# TAUV-Disconnect.net
KiCad netlist of a schematic drawn in Altium Designer
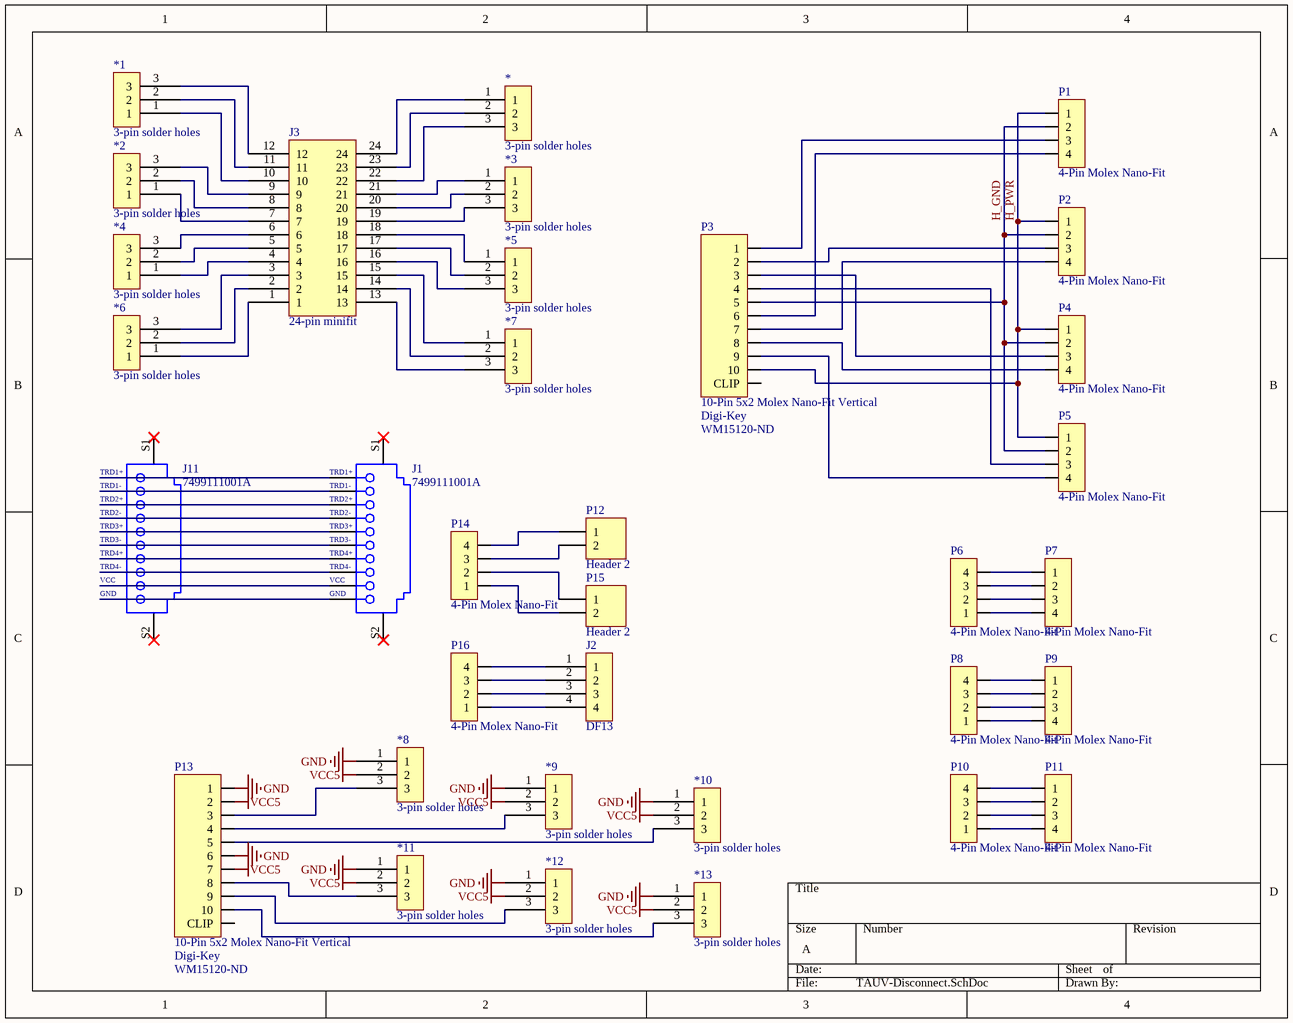
[diagram p0: TAUV-Disconnect.SchDoc]

(export (version "E")
  (design (tool "Eeschema 10.0.6"))
  (components
    (comp (ref "*")
      (value "3-pin solder holes")
      (footprint "3-PIN SOLDER HOLES")
      (libsource (lib "Tauv-Lib") (part "3-pin solder holes"))
    )
    (comp (ref "*1")
      (value "3-pin solder holes")
      (footprint "3-PIN SOLDER HOLES")
      (libsource (lib "") (part "3-pin solder holes_1"))
    )
    (comp (ref "*2")
      (value "3-pin solder holes")
      (footprint "3-PIN SOLDER HOLES")
      (libsource (lib "") (part "3-pin solder holes_1"))
    )
    (comp (ref "*3")
      (value "3-pin solder holes")
      (footprint "3-PIN SOLDER HOLES")
      (libsource (lib "Tauv-Lib") (part "3-pin solder holes"))
    )
    (comp (ref "*4")
      (value "3-pin solder holes")
      (footprint "3-PIN SOLDER HOLES")
      (libsource (lib "") (part "3-pin solder holes_1"))
    )
    (comp (ref "*5")
      (value "3-pin solder holes")
      (footprint "3-PIN SOLDER HOLES")
      (libsource (lib "Tauv-Lib") (part "3-pin solder holes"))
    )
    (comp (ref "*6")
      (value "3-pin solder holes")
      (footprint "3-PIN SOLDER HOLES")
      (libsource (lib "") (part "3-pin solder holes_1"))
    )
    (comp (ref "*7")
      (value "3-pin solder holes")
      (footprint "3-PIN SOLDER HOLES")
      (libsource (lib "Tauv-Lib") (part "3-pin solder holes"))
    )
    (comp (ref "*8")
      (value "3-pin solder holes")
      (footprint "3-PIN SOLDER HOLES - small")
      (libsource (lib "Tauv-Lib") (part "3-pin solder holes"))
    )
    (comp (ref "*9")
      (value "3-pin solder holes")
      (footprint "3-PIN SOLDER HOLES - small")
      (libsource (lib "Tauv-Lib") (part "3-pin solder holes"))
    )
    (comp (ref "*10")
      (value "3-pin solder holes")
      (footprint "3-PIN SOLDER HOLES - small")
      (libsource (lib "Tauv-Lib") (part "3-pin solder holes"))
    )
    (comp (ref "*11")
      (value "3-pin solder holes")
      (footprint "3-PIN SOLDER HOLES - small")
      (libsource (lib "Tauv-Lib") (part "3-pin solder holes"))
    )
    (comp (ref "*12")
      (value "3-pin solder holes")
      (footprint "3-PIN SOLDER HOLES - small")
      (libsource (lib "Tauv-Lib") (part "3-pin solder holes"))
    )
    (comp (ref "*13")
      (value "3-pin solder holes")
      (footprint "3-PIN SOLDER HOLES - small")
      (libsource (lib "Tauv-Lib") (part "3-pin solder holes"))
    )
    (comp (ref "J1")
      (value "7499111001A")
      (footprint "WE-7499111001A_V")
      (description "RJ45 LAN Transformer, Modular JACK, 0 to 70 degC, 10-Pin THD, RoHS, Tube")
      (libsource (lib "Altium Content Vault") (part "RJ45-10-2SHLD_A"))
    )
    (comp (ref "J2")
      (value "DF13")
      (footprint "4-pin DF13 vertical smd")
      (description "H126000CT-ND")
      (libsource (lib "Tauv-Lib") (part "4-pin DF13 vertical smd"))
    )
    (comp (ref "J3")
      (value "24-pin minifit")
      (footprint "24-PIN MINIFIT VERT")
      (description "RA: WM21362-ND\r\nVERT: WM3811-ND")
      (libsource (lib "Tauv-Lib") (part "24-pin minifit RA"))
    )
    (comp (ref "J11")
      (value "7499111001A")
      (footprint "WE-7499111001A_V")
      (description "RJ45 LAN Transformer, Modular JACK, 0 to 70 degC, 10-Pin THD, RoHS, Tube")
      (libsource (lib "Altium Content Vault") (part "RJ45-10-2SHLD_A"))
    )
    (comp (ref "P1")
      (value "4-Pin Molex Nano-Fit")
      (footprint "MOLEX NANO-FIT 1X4 - Vertical")
      (description "NanoFit ST Hdr TH SR 4Ckt")
      (fields (field (name "MANUFACTURER") "Molex") (field (name "PART NUMBER") "105313-1204"))
      (libsource (lib "") (part "4-Pin Nano-Fit Throughole Vertical_1"))
    )
    (comp (ref "P2")
      (value "4-Pin Molex Nano-Fit")
      (footprint "MOLEX NANO-FIT 1X4 - Vertical")
      (description "NanoFit ST Hdr TH SR 4Ckt")
      (fields (field (name "MANUFACTURER") "Molex") (field (name "PART NUMBER") "105313-1204"))
      (libsource (lib "") (part "4-Pin Nano-Fit Throughole Vertical_1"))
    )
    (comp (ref "P3")
      (value "10-Pin 5x2 Molex Nano-Fit Vertical")
      (footprint "MOLEX NANO-FIT 2x5 - Vertical")
      (description "NanoFit VT Hdr TH DR 10Ckt")
      (fields
        (field (name "PART NUMBER") "105314-1216")
        (field (name "MANUFACTURER") "Molex")
        (field (name "SUPPLIER 1") "Digi-Key")
        (field (name "SUPPLIER PART NUMBER 1") "WM15120-ND")
      )
      (libsource (lib "CMR_Connectors") (part "10-Pin 2-Row Nano-Fit_Vertical"))
    )
    (comp (ref "P4")
      (value "4-Pin Molex Nano-Fit")
      (footprint "MOLEX NANO-FIT 1X4 - Vertical")
      (description "NanoFit ST Hdr TH SR 4Ckt")
      (fields (field (name "MANUFACTURER") "Molex") (field (name "PART NUMBER") "105313-1204"))
      (libsource (lib "") (part "4-Pin Nano-Fit Throughole Vertical_1"))
    )
    (comp (ref "P5")
      (value "4-Pin Molex Nano-Fit")
      (footprint "MOLEX NANO-FIT 1X4 - Vertical")
      (description "NanoFit ST Hdr TH SR 4Ckt")
      (fields (field (name "MANUFACTURER") "Molex") (field (name "PART NUMBER") "105313-1204"))
      (libsource (lib "") (part "4-Pin Nano-Fit Throughole Vertical_1"))
    )
    (comp (ref "P6")
      (value "4-Pin Molex Nano-Fit")
      (footprint "MOLEX NANO-FIT 1X4 - Vertical")
      (description "NanoFit ST Hdr TH SR 4Ckt")
      (fields (field (name "MANUFACTURER") "Molex") (field (name "PART NUMBER") "105313-1204"))
      (libsource (lib "CMR_Connectors") (part "4-Pin Nano-Fit Throughole Vertical"))
    )
    (comp (ref "P7")
      (value "4-Pin Molex Nano-Fit")
      (footprint "MOLEX NANO-FIT 1X4 - Vertical")
      (description "NanoFit ST Hdr TH SR 4Ckt")
      (fields (field (name "MANUFACTURER") "Molex") (field (name "PART NUMBER") "105313-1204"))
      (libsource (lib "") (part "4-Pin Nano-Fit Throughole Vertical_1"))
    )
    (comp (ref "P8")
      (value "4-Pin Molex Nano-Fit")
      (footprint "MOLEX NANO-FIT 1X4 - Vertical")
      (description "NanoFit ST Hdr TH SR 4Ckt")
      (fields (field (name "MANUFACTURER") "Molex") (field (name "PART NUMBER") "105313-1204"))
      (libsource (lib "CMR_Connectors") (part "4-Pin Nano-Fit Throughole Vertical"))
    )
    (comp (ref "P9")
      (value "4-Pin Molex Nano-Fit")
      (footprint "MOLEX NANO-FIT 1X4 - Vertical")
      (description "NanoFit ST Hdr TH SR 4Ckt")
      (fields (field (name "MANUFACTURER") "Molex") (field (name "PART NUMBER") "105313-1204"))
      (libsource (lib "") (part "4-Pin Nano-Fit Throughole Vertical_1"))
    )
    (comp (ref "P10")
      (value "4-Pin Molex Nano-Fit")
      (footprint "MOLEX NANO-FIT 1X4 - Vertical")
      (description "NanoFit ST Hdr TH SR 4Ckt")
      (fields (field (name "MANUFACTURER") "Molex") (field (name "PART NUMBER") "105313-1204"))
      (libsource (lib "CMR_Connectors") (part "4-Pin Nano-Fit Throughole Vertical"))
    )
    (comp (ref "P11")
      (value "4-Pin Molex Nano-Fit")
      (footprint "MOLEX NANO-FIT 1X4 - Vertical")
      (description "NanoFit ST Hdr TH SR 4Ckt")
      (fields (field (name "MANUFACTURER") "Molex") (field (name "PART NUMBER") "105313-1204"))
      (libsource (lib "") (part "4-Pin Nano-Fit Throughole Vertical_1"))
    )
    (comp (ref "P12")
      (value "Header 2")
      (footprint "HDR1X2")
      (description "Header, 2-Pin")
      (fields (field (name "PUBLISHER") "Altium Limited"))
      (libsource (lib "Miscellaneous Connectors") (part "Header 2"))
    )
    (comp (ref "P13")
      (value "10-Pin 5x2 Molex Nano-Fit Vertical")
      (footprint "MOLEX NANO-FIT 2x5 - Vertical")
      (description "NanoFit VT Hdr TH DR 10Ckt")
      (fields
        (field (name "PART NUMBER") "105314-1216")
        (field (name "MANUFACTURER") "Molex")
        (field (name "SUPPLIER 1") "Digi-Key")
        (field (name "SUPPLIER PART NUMBER 1") "WM15120-ND")
      )
      (libsource (lib "CMR_Connectors") (part "10-Pin 2-Row Nano-Fit_Vertical"))
    )
    (comp (ref "P14")
      (value "4-Pin Molex Nano-Fit")
      (footprint "MOLEX NANO-FIT 1X4 - Vertical")
      (description "NanoFit ST Hdr TH SR 4Ckt")
      (fields (field (name "MANUFACTURER") "Molex") (field (name "PART NUMBER") "105313-1204"))
      (libsource (lib "CMR_Connectors") (part "4-Pin Nano-Fit Throughole Vertical"))
    )
    (comp (ref "P15")
      (value "Header 2")
      (footprint "HDR1X2")
      (description "Header, 2-Pin")
      (fields (field (name "PUBLISHER") "Altium Limited"))
      (libsource (lib "Miscellaneous Connectors") (part "Header 2"))
    )
    (comp (ref "P16")
      (value "4-Pin Molex Nano-Fit")
      (footprint "MOLEX NANO-FIT 1X4 - Vertical")
      (description "NanoFit ST Hdr TH SR 4Ckt")
      (fields (field (name "MANUFACTURER") "Molex") (field (name "PART NUMBER") "105313-1204"))
      (libsource (lib "CMR_Connectors") (part "4-Pin Nano-Fit Throughole Vertical"))
    )
  )
  (nets
    (net (code "1") (name "/H_GND") (class "Default")
      (node (ref "P1") (pin "2") (pinfunction "2_2") (pintype "passive"))
      (node (ref "P2") (pin "2") (pinfunction "2_2") (pintype "passive"))
      (node (ref "P3") (pin "5") (pinfunction "5_5") (pintype "passive"))
      (node (ref "P4") (pin "2") (pinfunction "2_2") (pintype "passive"))
      (node (ref "P5") (pin "2") (pinfunction "2_2") (pintype "passive"))
    )
    (net (code "2") (name "/H_PWR") (class "Default")
      (node (ref "P1") (pin "1") (pinfunction "1_1") (pintype "passive"))
      (node (ref "P2") (pin "1") (pinfunction "1_1") (pintype "passive"))
      (node (ref "P3") (pin "10") (pinfunction "10_10") (pintype "passive"))
      (node (ref "P4") (pin "1") (pinfunction "1_1") (pintype "passive"))
      (node (ref "P5") (pin "1") (pinfunction "1_1") (pintype "passive"))
    )
    (net (code "3") (name "GND") (class "Default")
      (node (ref "*10") (pin "1") (pinfunction "1_1") (pintype "passive"))
      (node (ref "*11") (pin "1") (pinfunction "1_1") (pintype "passive"))
      (node (ref "*12") (pin "1") (pinfunction "1_1") (pintype "passive"))
      (node (ref "*13") (pin "1") (pinfunction "1_1") (pintype "passive"))
      (node (ref "*8") (pin "1") (pinfunction "1_1") (pintype "passive"))
      (node (ref "*9") (pin "1") (pinfunction "1_1") (pintype "passive"))
      (node (ref "P13") (pin "1") (pinfunction "1_1") (pintype "passive"))
      (node (ref "P13") (pin "6") (pinfunction "6_6") (pintype "passive"))
    )
    (net (code "4") (name "Net-(*-Pad1)") (class "Default")
      (node (ref "*") (pin "1") (pinfunction "1_1") (pintype "passive"))
      (node (ref "J3") (pin "24") (pinfunction "24_24") (pintype "passive"))
    )
    (net (code "5") (name "Net-(*-Pad2)") (class "Default")
      (node (ref "*") (pin "2") (pinfunction "2_2") (pintype "passive"))
      (node (ref "J3") (pin "23") (pinfunction "23_23") (pintype "passive"))
    )
    (net (code "6") (name "Net-(*-Pad3)") (class "Default")
      (node (ref "*") (pin "3") (pinfunction "3_3") (pintype "passive"))
      (node (ref "J3") (pin "22") (pinfunction "22_22") (pintype "passive"))
    )
    (net (code "7") (name "Net-(*1-Pad1)") (class "Default")
      (node (ref "*1") (pin "1") (pinfunction "1_1") (pintype "passive"))
      (node (ref "J3") (pin "10") (pinfunction "10_10") (pintype "passive"))
    )
    (net (code "8") (name "Net-(*1-Pad2)") (class "Default")
      (node (ref "*1") (pin "2") (pinfunction "2_2") (pintype "passive"))
      (node (ref "J3") (pin "11") (pinfunction "11_11") (pintype "passive"))
    )
    (net (code "9") (name "Net-(*1-Pad3)") (class "Default")
      (node (ref "*1") (pin "3") (pinfunction "3_3") (pintype "passive"))
      (node (ref "J3") (pin "12") (pinfunction "12_12") (pintype "passive"))
    )
    (net (code "10") (name "Net-(*2-Pad1)") (class "Default")
      (node (ref "*2") (pin "1") (pinfunction "1_1") (pintype "passive"))
      (node (ref "J3") (pin "7") (pinfunction "7_7") (pintype "passive"))
    )
    (net (code "11") (name "Net-(*2-Pad2)") (class "Default")
      (node (ref "*2") (pin "2") (pinfunction "2_2") (pintype "passive"))
      (node (ref "J3") (pin "8") (pinfunction "8_8") (pintype "passive"))
    )
    (net (code "12") (name "Net-(*2-Pad3)") (class "Default")
      (node (ref "*2") (pin "3") (pinfunction "3_3") (pintype "passive"))
      (node (ref "J3") (pin "9") (pinfunction "9_9") (pintype "passive"))
    )
    (net (code "13") (name "Net-(*3-Pad1)") (class "Default")
      (node (ref "*3") (pin "1") (pinfunction "1_1") (pintype "passive"))
      (node (ref "J3") (pin "21") (pinfunction "21_21") (pintype "passive"))
    )
    (net (code "14") (name "Net-(*3-Pad2)") (class "Default")
      (node (ref "*3") (pin "2") (pinfunction "2_2") (pintype "passive"))
      (node (ref "J3") (pin "20") (pinfunction "20_20") (pintype "passive"))
    )
    (net (code "15") (name "Net-(*3-Pad3)") (class "Default")
      (node (ref "*3") (pin "3") (pinfunction "3_3") (pintype "passive"))
      (node (ref "J3") (pin "19") (pinfunction "19_19") (pintype "passive"))
    )
    (net (code "16") (name "Net-(*4-Pad1)") (class "Default")
      (node (ref "*4") (pin "1") (pinfunction "1_1") (pintype "passive"))
      (node (ref "J3") (pin "4") (pinfunction "4_4") (pintype "passive"))
    )
    (net (code "17") (name "Net-(*4-Pad2)") (class "Default")
      (node (ref "*4") (pin "2") (pinfunction "2_2") (pintype "passive"))
      (node (ref "J3") (pin "5") (pinfunction "5_5") (pintype "passive"))
    )
    (net (code "18") (name "Net-(*4-Pad3)") (class "Default")
      (node (ref "*4") (pin "3") (pinfunction "3_3") (pintype "passive"))
      (node (ref "J3") (pin "6") (pinfunction "6_6") (pintype "passive"))
    )
    (net (code "19") (name "Net-(*5-Pad1)") (class "Default")
      (node (ref "*5") (pin "1") (pinfunction "1_1") (pintype "passive"))
      (node (ref "J3") (pin "18") (pinfunction "18_18") (pintype "passive"))
    )
    (net (code "20") (name "Net-(*5-Pad2)") (class "Default")
      (node (ref "*5") (pin "2") (pinfunction "2_2") (pintype "passive"))
      (node (ref "J3") (pin "17") (pinfunction "17_17") (pintype "passive"))
    )
    (net (code "21") (name "Net-(*5-Pad3)") (class "Default")
      (node (ref "*5") (pin "3") (pinfunction "3_3") (pintype "passive"))
      (node (ref "J3") (pin "16") (pinfunction "16_16") (pintype "passive"))
    )
    (net (code "22") (name "Net-(*6-Pad1)") (class "Default")
      (node (ref "*6") (pin "1") (pinfunction "1_1") (pintype "passive"))
      (node (ref "J3") (pin "1") (pinfunction "1_1") (pintype "passive"))
    )
    (net (code "23") (name "Net-(*6-Pad2)") (class "Default")
      (node (ref "*6") (pin "2") (pinfunction "2_2") (pintype "passive"))
      (node (ref "J3") (pin "2") (pinfunction "2_2") (pintype "passive"))
    )
    (net (code "24") (name "Net-(*6-Pad3)") (class "Default")
      (node (ref "*6") (pin "3") (pinfunction "3_3") (pintype "passive"))
      (node (ref "J3") (pin "3") (pinfunction "3_3") (pintype "passive"))
    )
    (net (code "25") (name "Net-(*7-Pad1)") (class "Default")
      (node (ref "*7") (pin "1") (pinfunction "1_1") (pintype "passive"))
      (node (ref "J3") (pin "15") (pinfunction "15_15") (pintype "passive"))
    )
    (net (code "26") (name "Net-(*7-Pad2)") (class "Default")
      (node (ref "*7") (pin "2") (pinfunction "2_2") (pintype "passive"))
      (node (ref "J3") (pin "14") (pinfunction "14_14") (pintype "passive"))
    )
    (net (code "27") (name "Net-(*7-Pad3)") (class "Default")
      (node (ref "*7") (pin "3") (pinfunction "3_3") (pintype "passive"))
      (node (ref "J3") (pin "13") (pinfunction "13_13") (pintype "passive"))
    )
    (net (code "28") (name "Net-(*8-Pad3)") (class "Default")
      (node (ref "*8") (pin "3") (pinfunction "3_3") (pintype "passive"))
      (node (ref "P13") (pin "3") (pinfunction "3_3") (pintype "passive"))
    )
    (net (code "29") (name "Net-(*9-Pad3)") (class "Default")
      (node (ref "*9") (pin "3") (pinfunction "3_3") (pintype "passive"))
      (node (ref "P13") (pin "4") (pinfunction "4_4") (pintype "passive"))
    )
    (net (code "30") (name "Net-(*10-Pad3)") (class "Default")
      (node (ref "*10") (pin "3") (pinfunction "3_3") (pintype "passive"))
      (node (ref "P13") (pin "5") (pinfunction "5_5") (pintype "passive"))
    )
    (net (code "31") (name "Net-(*11-Pad3)") (class "Default")
      (node (ref "*11") (pin "3") (pinfunction "3_3") (pintype "passive"))
      (node (ref "P13") (pin "8") (pinfunction "8_8") (pintype "passive"))
    )
    (net (code "32") (name "Net-(*12-Pad3)") (class "Default")
      (node (ref "*12") (pin "3") (pinfunction "3_3") (pintype "passive"))
      (node (ref "P13") (pin "9") (pinfunction "9_9") (pintype "passive"))
    )
    (net (code "33") (name "Net-(*13-Pad3)") (class "Default")
      (node (ref "*13") (pin "3") (pinfunction "3_3") (pintype "passive"))
      (node (ref "P13") (pin "10") (pinfunction "10_10") (pintype "passive"))
    )
    (net (code "34") (name "Net-(J1-GND)") (class "Default")
      (node (ref "J1") (pin "10") (pinfunction "GND_10") (pintype "power_in"))
      (node (ref "J11") (pin "10") (pinfunction "GND_10") (pintype "power_in"))
    )
    (net (code "35") (name "Net-(J1-TRD1+)") (class "Default")
      (node (ref "J1") (pin "1") (pinfunction "TRD1+_1") (pintype "passive"))
      (node (ref "J11") (pin "1") (pinfunction "TRD1+_1") (pintype "passive"))
    )
    (net (code "36") (name "Net-(J1-TRD1-)") (class "Default")
      (node (ref "J1") (pin "2") (pinfunction "TRD1-_2") (pintype "passive"))
      (node (ref "J11") (pin "2") (pinfunction "TRD1-_2") (pintype "passive"))
    )
    (net (code "37") (name "Net-(J1-TRD2+)") (class "Default")
      (node (ref "J1") (pin "3") (pinfunction "TRD2+_3") (pintype "passive"))
      (node (ref "J11") (pin "3") (pinfunction "TRD2+_3") (pintype "passive"))
    )
    (net (code "38") (name "Net-(J1-TRD2-)") (class "Default")
      (node (ref "J1") (pin "4") (pinfunction "TRD2-_4") (pintype "passive"))
      (node (ref "J11") (pin "4") (pinfunction "TRD2-_4") (pintype "passive"))
    )
    (net (code "39") (name "Net-(J1-TRD3+)") (class "Default")
      (node (ref "J1") (pin "5") (pinfunction "TRD3+_5") (pintype "passive"))
      (node (ref "J11") (pin "5") (pinfunction "TRD3+_5") (pintype "passive"))
    )
    (net (code "40") (name "Net-(J1-TRD3-)") (class "Default")
      (node (ref "J1") (pin "6") (pinfunction "TRD3-_6") (pintype "passive"))
      (node (ref "J11") (pin "6") (pinfunction "TRD3-_6") (pintype "passive"))
    )
    (net (code "41") (name "Net-(J1-TRD4+)") (class "Default")
      (node (ref "J1") (pin "7") (pinfunction "TRD4+_7") (pintype "passive"))
      (node (ref "J11") (pin "7") (pinfunction "TRD4+_7") (pintype "passive"))
    )
    (net (code "42") (name "Net-(J1-TRD4-)") (class "Default")
      (node (ref "J1") (pin "8") (pinfunction "TRD4-_8") (pintype "passive"))
      (node (ref "J11") (pin "8") (pinfunction "TRD4-_8") (pintype "passive"))
    )
    (net (code "43") (name "Net-(J1-VCC)") (class "Default")
      (node (ref "J1") (pin "9") (pinfunction "VCC_9") (pintype "power_in"))
      (node (ref "J11") (pin "9") (pinfunction "VCC_9") (pintype "power_in"))
    )
    (net (code "44") (name "Net-(J2-Pad1)") (class "Default")
      (node (ref "J2") (pin "1") (pinfunction "1_1") (pintype "passive"))
      (node (ref "P16") (pin "4") (pinfunction "4_4") (pintype "passive"))
    )
    (net (code "45") (name "Net-(J2-Pad2)") (class "Default")
      (node (ref "J2") (pin "2") (pinfunction "2_2") (pintype "passive"))
      (node (ref "P16") (pin "3") (pinfunction "3_3") (pintype "passive"))
    )
    (net (code "46") (name "Net-(J2-Pad3)") (class "Default")
      (node (ref "J2") (pin "3") (pinfunction "3_3") (pintype "passive"))
      (node (ref "P16") (pin "2") (pinfunction "2_2") (pintype "passive"))
    )
    (net (code "47") (name "Net-(J2-Pad4)") (class "Default")
      (node (ref "J2") (pin "4") (pinfunction "4_4") (pintype "passive"))
      (node (ref "P16") (pin "1") (pinfunction "1_1") (pintype "passive"))
    )
    (net (code "48") (name "Net-(P1-Pad3)") (class "Default")
      (node (ref "P1") (pin "3") (pinfunction "3_3") (pintype "passive"))
      (node (ref "P3") (pin "1") (pinfunction "1_1") (pintype "passive"))
    )
    (net (code "49") (name "Net-(P1-Pad4)") (class "Default")
      (node (ref "P1") (pin "4") (pinfunction "4_4") (pintype "passive"))
      (node (ref "P3") (pin "6") (pinfunction "6_6") (pintype "passive"))
    )
    (net (code "50") (name "Net-(P2-Pad3)") (class "Default")
      (node (ref "P2") (pin "3") (pinfunction "3_3") (pintype "passive"))
      (node (ref "P3") (pin "2") (pinfunction "2_2") (pintype "passive"))
    )
    (net (code "51") (name "Net-(P2-Pad4)") (class "Default")
      (node (ref "P2") (pin "4") (pinfunction "4_4") (pintype "passive"))
      (node (ref "P3") (pin "7") (pinfunction "7_7") (pintype "passive"))
    )
    (net (code "52") (name "Net-(P3-Pad3)") (class "Default")
      (node (ref "P3") (pin "3") (pinfunction "3_3") (pintype "passive"))
      (node (ref "P4") (pin "3") (pinfunction "3_3") (pintype "passive"))
    )
    (net (code "53") (name "Net-(P3-Pad4)") (class "Default")
      (node (ref "P3") (pin "4") (pinfunction "4_4") (pintype "passive"))
      (node (ref "P5") (pin "3") (pinfunction "3_3") (pintype "passive"))
    )
    (net (code "54") (name "Net-(P3-Pad8)") (class "Default")
      (node (ref "P3") (pin "8") (pinfunction "8_8") (pintype "passive"))
      (node (ref "P4") (pin "4") (pinfunction "4_4") (pintype "passive"))
    )
    (net (code "55") (name "Net-(P3-Pad9)") (class "Default")
      (node (ref "P3") (pin "9") (pinfunction "9_9") (pintype "passive"))
      (node (ref "P5") (pin "4") (pinfunction "4_4") (pintype "passive"))
    )
    (net (code "56") (name "Net-(P6-Pad1)") (class "Default")
      (node (ref "P6") (pin "1") (pinfunction "1_1") (pintype "passive"))
      (node (ref "P7") (pin "4") (pinfunction "4_4") (pintype "passive"))
    )
    (net (code "57") (name "Net-(P6-Pad2)") (class "Default")
      (node (ref "P6") (pin "2") (pinfunction "2_2") (pintype "passive"))
      (node (ref "P7") (pin "3") (pinfunction "3_3") (pintype "passive"))
    )
    (net (code "58") (name "Net-(P6-Pad3)") (class "Default")
      (node (ref "P6") (pin "3") (pinfunction "3_3") (pintype "passive"))
      (node (ref "P7") (pin "2") (pinfunction "2_2") (pintype "passive"))
    )
    (net (code "59") (name "Net-(P6-Pad4)") (class "Default")
      (node (ref "P6") (pin "4") (pinfunction "4_4") (pintype "passive"))
      (node (ref "P7") (pin "1") (pinfunction "1_1") (pintype "passive"))
    )
    (net (code "60") (name "Net-(P8-Pad1)") (class "Default")
      (node (ref "P8") (pin "1") (pinfunction "1_1") (pintype "passive"))
      (node (ref "P9") (pin "4") (pinfunction "4_4") (pintype "passive"))
    )
    (net (code "61") (name "Net-(P8-Pad2)") (class "Default")
      (node (ref "P8") (pin "2") (pinfunction "2_2") (pintype "passive"))
      (node (ref "P9") (pin "3") (pinfunction "3_3") (pintype "passive"))
    )
    (net (code "62") (name "Net-(P8-Pad3)") (class "Default")
      (node (ref "P8") (pin "3") (pinfunction "3_3") (pintype "passive"))
      (node (ref "P9") (pin "2") (pinfunction "2_2") (pintype "passive"))
    )
    (net (code "63") (name "Net-(P8-Pad4)") (class "Default")
      (node (ref "P8") (pin "4") (pinfunction "4_4") (pintype "passive"))
      (node (ref "P9") (pin "1") (pinfunction "1_1") (pintype "passive"))
    )
    (net (code "64") (name "Net-(P10-Pad1)") (class "Default")
      (node (ref "P10") (pin "1") (pinfunction "1_1") (pintype "passive"))
      (node (ref "P11") (pin "4") (pinfunction "4_4") (pintype "passive"))
    )
    (net (code "65") (name "Net-(P10-Pad2)") (class "Default")
      (node (ref "P10") (pin "2") (pinfunction "2_2") (pintype "passive"))
      (node (ref "P11") (pin "3") (pinfunction "3_3") (pintype "passive"))
    )
    (net (code "66") (name "Net-(P10-Pad3)") (class "Default")
      (node (ref "P10") (pin "3") (pinfunction "3_3") (pintype "passive"))
      (node (ref "P11") (pin "2") (pinfunction "2_2") (pintype "passive"))
    )
    (net (code "67") (name "Net-(P10-Pad4)") (class "Default")
      (node (ref "P10") (pin "4") (pinfunction "4_4") (pintype "passive"))
      (node (ref "P11") (pin "1") (pinfunction "1_1") (pintype "passive"))
    )
    (net (code "68") (name "Net-(P12-Pad1)") (class "Default")
      (node (ref "P12") (pin "1") (pinfunction "1_1") (pintype "passive"))
      (node (ref "P14") (pin "4") (pinfunction "4_4") (pintype "passive"))
    )
    (net (code "69") (name "Net-(P12-Pad2)") (class "Default")
      (node (ref "P12") (pin "2") (pinfunction "2_2") (pintype "passive"))
      (node (ref "P14") (pin "3") (pinfunction "3_3") (pintype "passive"))
    )
    (net (code "70") (name "Net-(P14-Pad1)") (class "Default")
      (node (ref "P14") (pin "1") (pinfunction "1_1") (pintype "passive"))
      (node (ref "P15") (pin "2") (pinfunction "2_2") (pintype "passive"))
    )
    (net (code "71") (name "Net-(P14-Pad2)") (class "Default")
      (node (ref "P14") (pin "2") (pinfunction "2_2") (pintype "passive"))
      (node (ref "P15") (pin "1") (pinfunction "1_1") (pintype "passive"))
    )
    (net (code "72") (name "VCC5") (class "Default")
      (node (ref "*10") (pin "2") (pinfunction "2_2") (pintype "passive"))
      (node (ref "*11") (pin "2") (pinfunction "2_2") (pintype "passive"))
      (node (ref "*12") (pin "2") (pinfunction "2_2") (pintype "passive"))
      (node (ref "*13") (pin "2") (pinfunction "2_2") (pintype "passive"))
      (node (ref "*8") (pin "2") (pinfunction "2_2") (pintype "passive"))
      (node (ref "*9") (pin "2") (pinfunction "2_2") (pintype "passive"))
      (node (ref "P13") (pin "2") (pinfunction "2_2") (pintype "passive"))
      (node (ref "P13") (pin "7") (pinfunction "7_7") (pintype "passive"))
    )
    (net (code "73") (name "unconnected-(J1-SHLD-PadS1)") (class "Default")
      (node (ref "J1") (pin "S1") (pinfunction "SHLD_S1") (pintype "passive+no_connect"))
    )
    (net (code "74") (name "unconnected-(J1-SHLD-PadS2)") (class "Default")
      (node (ref "J1") (pin "S2") (pinfunction "SHLD_S2") (pintype "passive+no_connect"))
    )
    (net (code "75") (name "unconnected-(J11-SHLD-PadS1)") (class "Default")
      (node (ref "J11") (pin "S1") (pinfunction "SHLD_S1") (pintype "passive+no_connect"))
    )
    (net (code "76") (name "unconnected-(J11-SHLD-PadS2)") (class "Default")
      (node (ref "J11") (pin "S2") (pinfunction "SHLD_S2") (pintype "passive+no_connect"))
    )
    (net (code "77") (name "unconnected-(P3-CLIP-Pad11)") (class "Default")
      (node (ref "P3") (pin "11") (pinfunction "CLIP_11") (pintype "passive"))
    )
    (net (code "78") (name "unconnected-(P13-CLIP-Pad11)") (class "Default")
      (node (ref "P13") (pin "11") (pinfunction "CLIP_11") (pintype "passive"))
    )
  )
)
